# ATX_Breakout.net
KiCad netlist of a schematic drawn in EAGLE
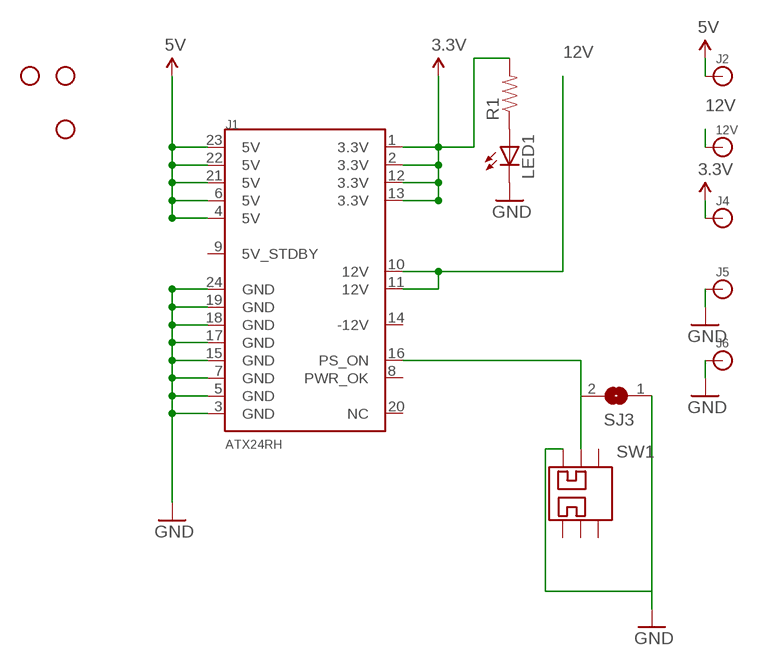
[diagram p0: schematic, sheet 1]

(export (version "E")
  (design (tool "Eeschema 10.0.6"))
  (components
    (comp (ref "12V")
      (value "BANANA_CONN")
      (footprint "eagle-import:BANANA_CONN")
      (libsource (lib "eagle-import") (part "BANANA_CONN"))
    )
    (comp (ref "J1")
      (value "ATX24RH")
      (footprint "eagle-import:ATX24_RIGHT_ANGLE")
      (libsource (lib "eagle-import") (part "ATX24RH"))
    )
    (comp (ref "J2")
      (value "BANANA_CONN")
      (footprint "eagle-import:BANANA_CONN")
      (libsource (lib "eagle-import") (part "BANANA_CONN"))
    )
    (comp (ref "J4")
      (value "BANANA_CONN")
      (footprint "eagle-import:BANANA_CONN")
      (libsource (lib "eagle-import") (part "BANANA_CONN"))
    )
    (comp (ref "J5")
      (value "BANANA_CONN")
      (footprint "eagle-import:BANANA_CONN")
      (libsource (lib "eagle-import") (part "BANANA_CONN"))
    )
    (comp (ref "J6")
      (value "BANANA_CONN")
      (footprint "eagle-import:BANANA_CONN")
      (libsource (lib "eagle-import") (part "BANANA_CONN"))
    )
    (comp (ref "JP1")
      (value "STAND-OFF")
      (footprint "eagle-import:STAND-OFF")
      (libsource (lib "eagle-import") (part "STAND-OFF"))
    )
    (comp (ref "JP2")
      (value "STAND-OFF")
      (footprint "eagle-import:STAND-OFF")
      (libsource (lib "eagle-import") (part "STAND-OFF"))
    )
    (comp (ref "JP3")
      (value "STAND-OFF")
      (footprint "eagle-import:STAND-OFF")
      (libsource (lib "eagle-import") (part "STAND-OFF"))
    )
    (comp (ref "LED1")
      (value "LED0805")
      (footprint "eagle-import:LED-0805")
      (libsource (lib "eagle-import") (part "LED0805"))
    )
    (comp (ref "R1")
      (value "RESISTOR0805-RES")
      (footprint "eagle-import:0805")
      (libsource (lib "eagle-import") (part "RESISTOR0805-RES"))
    )
    (comp (ref "SJ3") (value "SJ") (footprint "eagle-import:SJ") (libsource (lib "eagle-import") (part "SJ")))
    (comp (ref "SW1")
      (value "SLIDE_SWITCH_DPDTRA")
      (footprint "eagle-import:EG2219")
      (libsource (lib "eagle-import") (part "SLIDE_SWITCH_DPDTRA"))
    )
  )
  (nets
    (net (code "1") (name "/12V") (class "Default")
      (node (ref "12V") (pin "P$1") (pinfunction "1_P$1") (pintype "passive"))
      (node (ref "J1") (pin "10") (pinfunction "12V_10") (pintype "bidirectional"))
      (node (ref "J1") (pin "11") (pinfunction "12V_11") (pintype "bidirectional"))
    )
    (net (code "2") (name "3.3V") (class "Default")
      (node (ref "J1") (pin "1") (pinfunction "3.3V_1") (pintype "bidirectional"))
      (node (ref "J1") (pin "12") (pinfunction "3.3V_12") (pintype "bidirectional"))
      (node (ref "J1") (pin "13") (pinfunction "3.3V_13") (pintype "bidirectional"))
      (node (ref "J1") (pin "2") (pinfunction "3.3V_2") (pintype "bidirectional"))
      (node (ref "J4") (pin "P$1") (pinfunction "1_P$1") (pintype "passive"))
      (node (ref "R1") (pin "2") (pinfunction "2_2") (pintype "passive"))
    )
    (net (code "3") (name "5V") (class "Default")
      (node (ref "J1") (pin "21") (pinfunction "5V_21") (pintype "bidirectional"))
      (node (ref "J1") (pin "22") (pinfunction "5V_22") (pintype "bidirectional"))
      (node (ref "J1") (pin "23") (pinfunction "5V_23") (pintype "bidirectional"))
      (node (ref "J1") (pin "4") (pinfunction "5V_4") (pintype "bidirectional"))
      (node (ref "J1") (pin "6") (pinfunction "5V_6") (pintype "bidirectional"))
      (node (ref "J2") (pin "P$1") (pinfunction "1_P$1") (pintype "passive"))
    )
    (net (code "4") (name "GND") (class "Default")
      (node (ref "J1") (pin "15") (pinfunction "GND_15") (pintype "bidirectional"))
      (node (ref "J1") (pin "17") (pinfunction "GND_17") (pintype "bidirectional"))
      (node (ref "J1") (pin "18") (pinfunction "GND_18") (pintype "bidirectional"))
      (node (ref "J1") (pin "19") (pinfunction "GND_19") (pintype "bidirectional"))
      (node (ref "J1") (pin "24") (pinfunction "GND_24") (pintype "bidirectional"))
      (node (ref "J1") (pin "3") (pinfunction "GND_3") (pintype "bidirectional"))
      (node (ref "J1") (pin "5") (pinfunction "GND_5") (pintype "bidirectional"))
      (node (ref "J1") (pin "7") (pinfunction "GND_7") (pintype "bidirectional"))
      (node (ref "J5") (pin "P$1") (pinfunction "1_P$1") (pintype "passive"))
      (node (ref "J6") (pin "P$1") (pinfunction "1_P$1") (pintype "passive"))
      (node (ref "LED1") (pin "2") (pinfunction "C_2") (pintype "passive"))
      (node (ref "SJ3") (pin "1") (pinfunction "1_1") (pintype "passive"))
      (node (ref "SW1") (pin "P$1") (pinfunction "P$1_P$1") (pintype "bidirectional"))
    )
    (net (code "5") (name "Net-(J1-PS_ON)") (class "Default")
      (node (ref "J1") (pin "16") (pinfunction "PS_ON_16") (pintype "bidirectional"))
      (node (ref "SJ3") (pin "2") (pinfunction "2_2") (pintype "passive"))
      (node (ref "SW1") (pin "P$2") (pinfunction "P$2_P$2") (pintype "bidirectional"))
    )
    (net (code "6") (name "Net-(LED1-A)") (class "Default")
      (node (ref "LED1") (pin "1") (pinfunction "A_1") (pintype "passive"))
      (node (ref "R1") (pin "1") (pinfunction "1_1") (pintype "passive"))
    )
    (net (code "7") (name "unconnected-(J1--12V-Pad14)") (class "Default")
      (node (ref "J1") (pin "14") (pinfunction "-12V_14") (pintype "bidirectional"))
    )
    (net (code "8") (name "unconnected-(J1-5V_STDBY-Pad9)") (class "Default")
      (node (ref "J1") (pin "9") (pinfunction "5V_STDBY_9") (pintype "bidirectional"))
    )
    (net (code "9") (name "unconnected-(J1-NC-Pad20)") (class "Default")
      (node (ref "J1") (pin "20") (pinfunction "NC_20") (pintype "bidirectional"))
    )
    (net (code "10") (name "unconnected-(J1-PWR_OK-Pad8)") (class "Default")
      (node (ref "J1") (pin "8") (pinfunction "PWR_OK_8") (pintype "bidirectional"))
    )
    (net (code "11") (name "unconnected-(SW1-PadP$3)") (class "Default")
      (node (ref "SW1") (pin "P$3") (pinfunction "P$3_P$3") (pintype "bidirectional"))
    )
    (net (code "12") (name "unconnected-(SW1-PadP$4)") (class "Default")
      (node (ref "SW1") (pin "P$4") (pinfunction "P$4_P$4") (pintype "bidirectional"))
    )
    (net (code "13") (name "unconnected-(SW1-PadP$5)") (class "Default")
      (node (ref "SW1") (pin "P$5") (pinfunction "P$5_P$5") (pintype "bidirectional"))
    )
    (net (code "14") (name "unconnected-(SW1-PadP$6)") (class "Default")
      (node (ref "SW1") (pin "P$6") (pinfunction "P$6_P$6") (pintype "bidirectional"))
    )
  )
)
